# MT25QL256_QSPI_NOR_Flash.net
KiCad netlist of a schematic drawn in Altium Designer
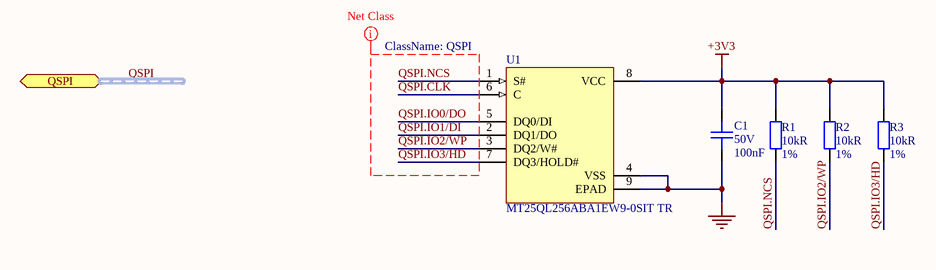
[diagram p0: MT25QL256_QSPI_NOR_Flash.SchDoc]

(export (version "E")
  (design (tool "Eeschema 10.0.6"))
  (components
    (comp (ref "C1")
      (value "CAP CER 0.1UF 50V X7R 0402")
      (footprint "C0402")
      (description "0.1µF ±10% 50V Ceramic Capacitor X7R 0402 (1005 Metric)")
      (fields
        (field (name "MANUFACTURER PART NUMBER") "CGA2B3X7R1H104K050BB")
        (field (name "MANUFACTURER") "TDK")
        (field (name "VOLTAGE") "50V")
        (field (name "CAPACITANCE") "100nF")
      )
      (libsource (lib "capacitors_smd") (part "CAP CER 0.1UF 50V X7R 0402"))
    )
    (comp (ref "R1")
      (value "RES SMD 10K OHM 1% 1/16W 0402")
      (footprint "R0402")
      (description "10 kOhms ±1% 0.063W, 1/16W Chip Resistor 0402 (1005 Metric) Moisture Resistant Thick Film")
      (fields
        (field (name "MANUFACTURER PART NUMBER") "RC0402FR-0710KP")
        (field (name "MANUFACTURER") "Yageo")
        (field (name "RESISTANCE") "10kR")
        (field (name "TOLERANCE") "1%")
      )
      (libsource (lib "resistors_smd") (part "RES SMD 10K OHM 1% 1/16W 0402"))
    )
    (comp (ref "R2")
      (value "RES SMD 10K OHM 1% 1/16W 0402")
      (footprint "R0402")
      (description "10 kOhms ±1% 0.063W, 1/16W Chip Resistor 0402 (1005 Metric) Moisture Resistant Thick Film")
      (fields
        (field (name "MANUFACTURER PART NUMBER") "RC0402FR-0710KP")
        (field (name "MANUFACTURER") "Yageo")
        (field (name "RESISTANCE") "10kR")
        (field (name "TOLERANCE") "1%")
      )
      (libsource (lib "resistors_smd") (part "RES SMD 10K OHM 1% 1/16W 0402"))
    )
    (comp (ref "R3")
      (value "RES SMD 10K OHM 1% 1/16W 0402")
      (footprint "R0402")
      (description "10 kOhms ±1% 0.063W, 1/16W Chip Resistor 0402 (1005 Metric) Moisture Resistant Thick Film")
      (fields
        (field (name "MANUFACTURER PART NUMBER") "RC0402FR-0710KP")
        (field (name "MANUFACTURER") "Yageo")
        (field (name "RESISTANCE") "10kR")
        (field (name "TOLERANCE") "1%")
      )
      (libsource (lib "resistors_smd") (part "RES SMD 10K OHM 1% 1/16W 0402"))
    )
    (comp (ref "U1")
      (value "MT25QL256ABA1EW9-0SIT TR")
      (footprint "W-PDFN-8_8X6_P127")
      (description "256Mb, 3V, Multiple I/O Serial Flash Memory, Quad/Dual")
      (fields (field (name "MANUFACTURER") "Micron Technology"))
      (libsource (lib "BLDC_Moto_Driver") (part "IC MT25QL256 FLASH 256M SPI 133MHZ 8WPDFN"))
    )
  )
  (nets
    (net (code "2") (name "+3V3") (class "Default")
      (node (ref "C1") (pin "2") (pinfunction "2_2") (pintype "passive"))
      (node (ref "R1") (pin "1") (pinfunction "1_1") (pintype "passive"))
      (node (ref "R2") (pin "1") (pinfunction "1_1") (pintype "passive"))
      (node (ref "R3") (pin "1") (pinfunction "1_1") (pintype "passive"))
      (node (ref "U1") (pin "8") (pinfunction "VCC_8") (pintype "passive"))
    )
    (net (code "3") (name "/QSPI.CLK") (class "Default")
      (node (ref "U1") (pin "6") (pinfunction "C_6") (pintype "input"))
    )
    (net (code "4") (name "/QSPI.IO0{slash}DO") (class "Default")
      (node (ref "U1") (pin "5") (pinfunction "DQ0/DI_5") (pintype "passive"))
    )
    (net (code "5") (name "/QSPI.IO1{slash}DI") (class "Default")
      (node (ref "U1") (pin "2") (pinfunction "DQ1/DO_2") (pintype "passive"))
    )
    (net (code "6") (name "/QSPI.IO2{slash}WP") (class "Default")
      (node (ref "R2") (pin "2") (pinfunction "2_2") (pintype "passive"))
      (node (ref "U1") (pin "3") (pinfunction "DQ2/W#_3") (pintype "passive"))
    )
    (net (code "7") (name "/QSPI.IO3{slash}HD") (class "Default")
      (node (ref "R3") (pin "2") (pinfunction "2_2") (pintype "passive"))
      (node (ref "U1") (pin "7") (pinfunction "DQ3/HOLD#_7") (pintype "passive"))
    )
    (net (code "8") (name "/QSPI.NCS") (class "Default")
      (node (ref "R1") (pin "2") (pinfunction "2_2") (pintype "passive"))
      (node (ref "U1") (pin "1") (pinfunction "S#_1") (pintype "input"))
    )
    (net (code "10") (name "GND") (class "Default")
      (node (ref "C1") (pin "1") (pinfunction "1_1") (pintype "passive"))
      (node (ref "U1") (pin "4") (pinfunction "VSS_4") (pintype "passive"))
      (node (ref "U1") (pin "9") (pinfunction "EPAD_9") (pintype "passive"))
    )
  )
)
